# BareBones_Arduino_No_Multiplexer.net
KiCad netlist of a schematic drawn in EAGLE
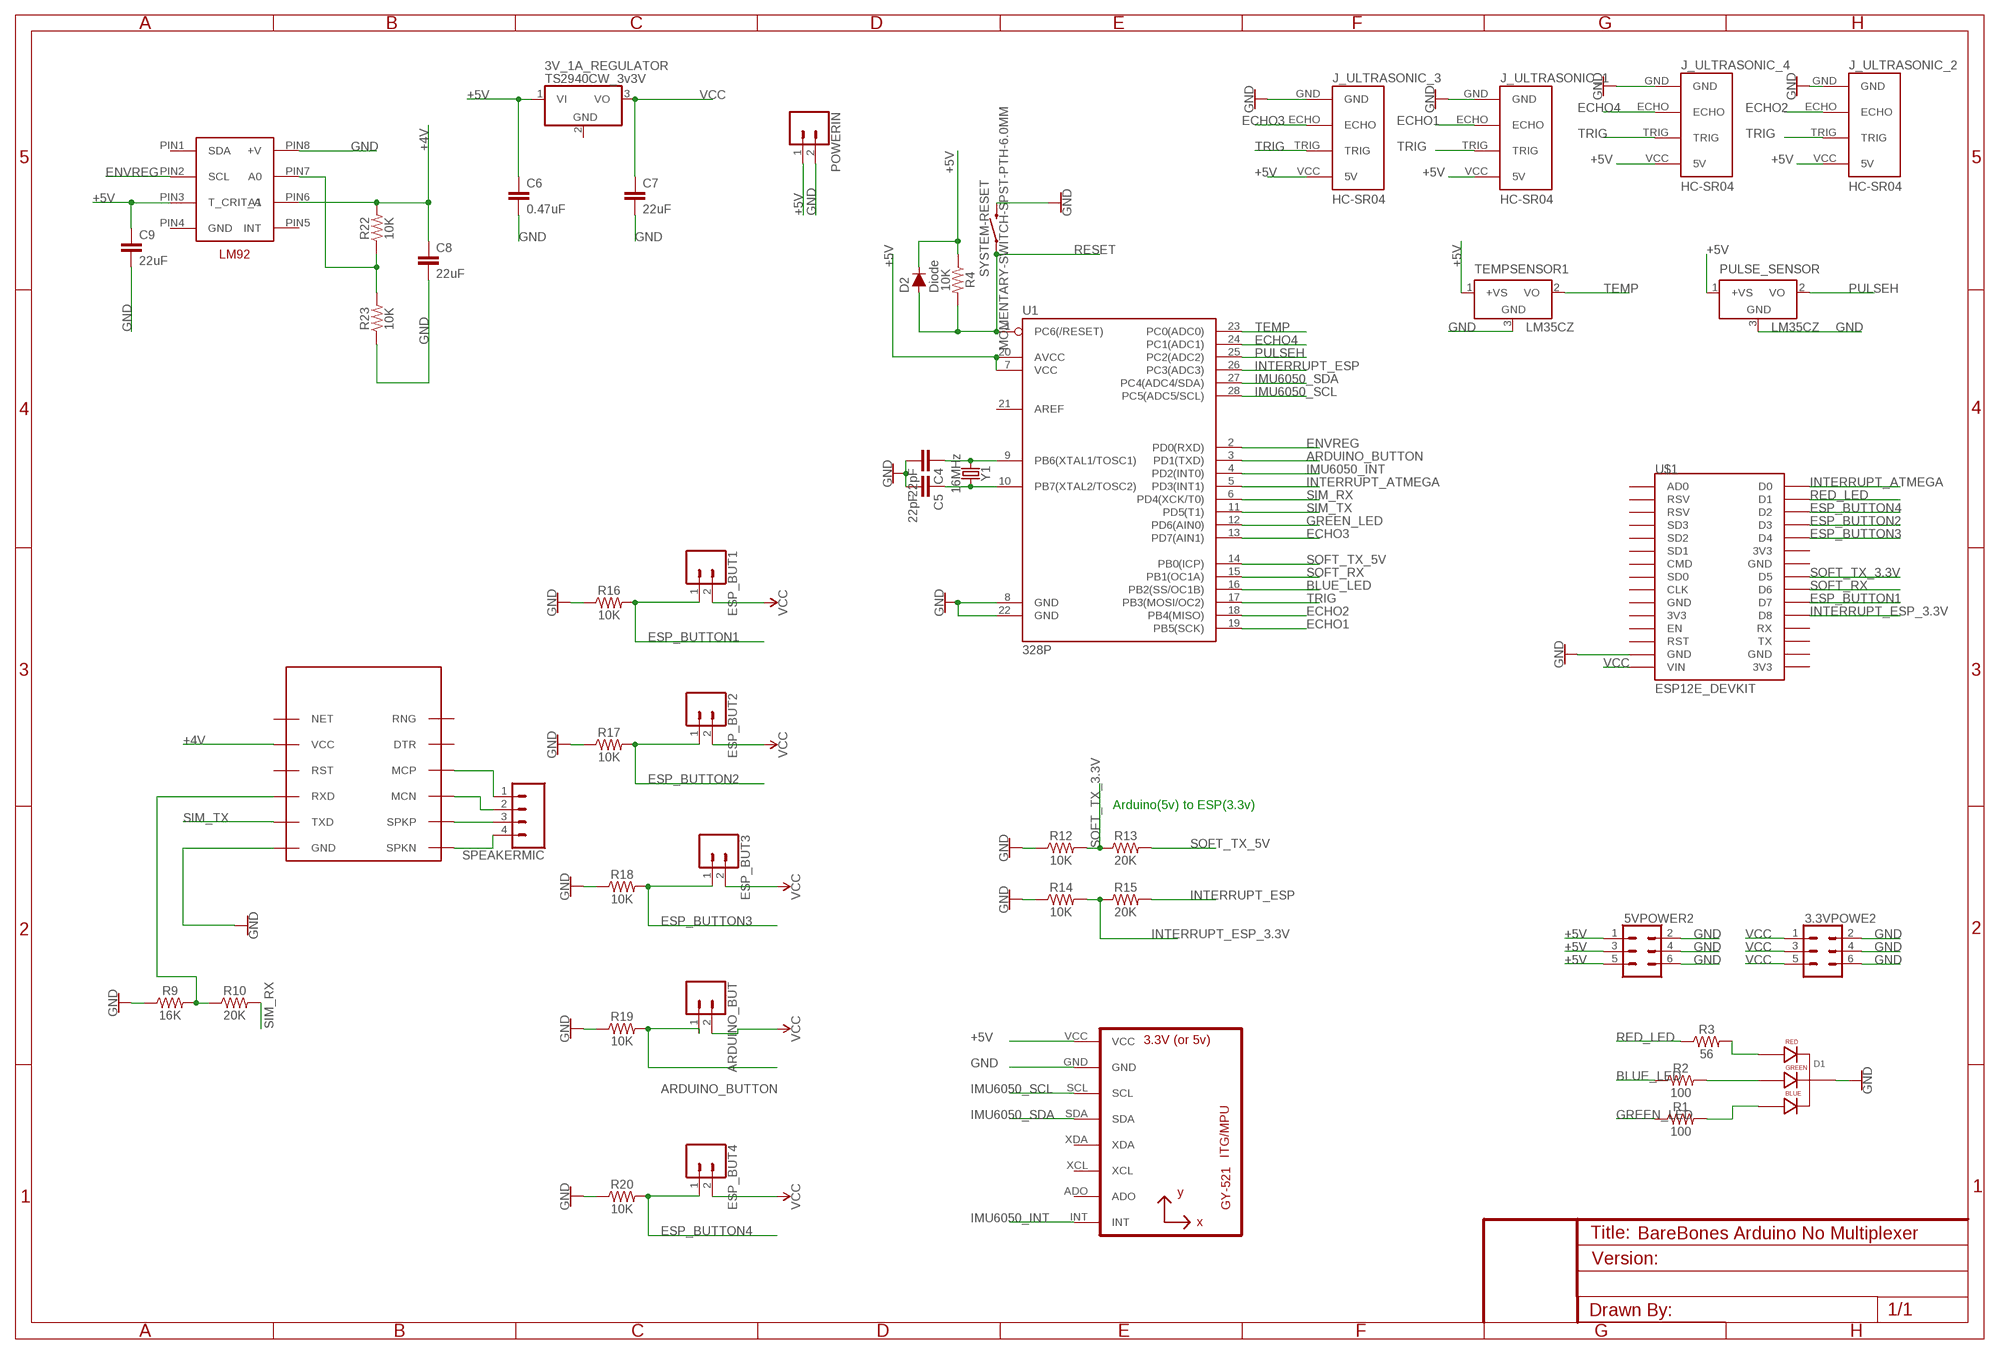
[diagram p0: schematic, sheet 1]

(export (version "E")
  (design (tool "Eeschema 10.0.6"))
  (components
    (comp (ref "3.3VPOWE2")
      (value "CONN_03X2FEMALE")
      (footprint "eagle-import:2X3")
      (libsource (lib "eagle-import") (part "CONN_03X2FEMALE"))
    )
    (comp (ref "3V_1A_REGULATOR")
      (value "TS2940CW_3v3V")
      (footprint "eagle-import:SOT223")
      (libsource (lib "eagle-import") (part "MCP1703DB"))
    )
    (comp (ref "5VPOWER2")
      (value "CONN_03X2FEMALE")
      (footprint "eagle-import:2X3")
      (libsource (lib "eagle-import") (part "CONN_03X2FEMALE"))
    )
    (comp (ref "ARDUINO_BUT")
      (value "CONN_02")
      (footprint "eagle-import:1X02")
      (libsource (lib "eagle-import") (part "CONN_02"))
    )
    (comp (ref "C4")
      (value "22pF")
      (footprint "eagle-import:CAP-PTH-2.54")
      (libsource (lib "eagle-import") (part "22PF-PTH-2.54MM-200V-5%"))
    )
    (comp (ref "C5")
      (value "22pF")
      (footprint "eagle-import:CAP-PTH-2.54")
      (libsource (lib "eagle-import") (part "22PF-PTH-2.54MM-200V-5%"))
    )
    (comp (ref "C6")
      (value "0.47uF")
      (footprint "eagle-import:CAP-PTH-SMALL-KIT")
      (libsource (lib "eagle-import") (part "0.1UF-KIT-EZ-50V-20%"))
    )
    (comp (ref "C7")
      (value "22uF")
      (footprint "eagle-import:CAP-PTH-SMALL-KIT")
      (libsource (lib "eagle-import") (part "0.1UF-KIT-EZ-50V-20%"))
    )
    (comp (ref "C8")
      (value "22uF")
      (footprint "eagle-import:CAP-PTH-SMALL-KIT")
      (libsource (lib "eagle-import") (part "0.1UF-KIT-EZ-50V-20%"))
    )
    (comp (ref "C9")
      (value "22uF")
      (footprint "eagle-import:CAP-PTH-SMALL-KIT")
      (libsource (lib "eagle-import") (part "0.1UF-KIT-EZ-50V-20%"))
    )
    (comp (ref "D1")
      (value "LED-RGB-CC-THRUDIFFUSE")
      (footprint "eagle-import:LED-RGB-THRU")
      (libsource (lib "eagle-import") (part "LED-RGB-CC-THRUDIFFUSE"))
    )
    (comp (ref "D2")
      (value "Diode")
      (footprint "eagle-import:DIODE-1N4148")
      (libsource (lib "eagle-import") (part "DIODE-1N4148"))
    )
    (comp (ref "ESP_BUT1")
      (value "CONN_02")
      (footprint "eagle-import:1X02")
      (libsource (lib "eagle-import") (part "CONN_02"))
    )
    (comp (ref "ESP_BUT2")
      (value "CONN_02")
      (footprint "eagle-import:1X02")
      (libsource (lib "eagle-import") (part "CONN_02"))
    )
    (comp (ref "ESP_BUT3")
      (value "CONN_02")
      (footprint "eagle-import:1X02")
      (libsource (lib "eagle-import") (part "CONN_02"))
    )
    (comp (ref "ESP_BUT4")
      (value "CONN_02")
      (footprint "eagle-import:1X02")
      (libsource (lib "eagle-import") (part "CONN_02"))
    )
    (comp (ref "J_ULTRASONIC_1")
      (value "HC-SR04")
      (footprint "eagle-import:HC-SR04_FOOTPRINT")
      (libsource (lib "eagle-import") (part "HC-SR04"))
    )
    (comp (ref "J_ULTRASONIC_2")
      (value "HC-SR04")
      (footprint "eagle-import:HC-SR04_FOOTPRINT")
      (libsource (lib "eagle-import") (part "HC-SR04"))
    )
    (comp (ref "J_ULTRASONIC_3")
      (value "HC-SR04")
      (footprint "eagle-import:HC-SR04_FOOTPRINT")
      (libsource (lib "eagle-import") (part "HC-SR04"))
    )
    (comp (ref "J_ULTRASONIC_4")
      (value "HC-SR04")
      (footprint "eagle-import:HC-SR04_FOOTPRINT")
      (libsource (lib "eagle-import") (part "HC-SR04"))
    )
    (comp (ref "POWERIN")
      (value "CONN_025MM")
      (footprint "eagle-import:SCREWTERMINAL-5MM-2")
      (libsource (lib "eagle-import") (part "CONN_025MM"))
    )
    (comp (ref "PULSE_SENSOR")
      (value "LM35CZ")
      (footprint "eagle-import:TO92")
      (libsource (lib "eagle-import") (part "LM35CZ"))
    )
    (comp (ref "R1")
      (value "100")
      (footprint "eagle-import:AXIAL-0.3")
      (libsource (lib "eagle-import") (part "100OHM-HORIZ-1/4W-1%"))
    )
    (comp (ref "R2")
      (value "100")
      (footprint "eagle-import:AXIAL-0.3")
      (libsource (lib "eagle-import") (part "100OHM-HORIZ-1/4W-1%"))
    )
    (comp (ref "R3")
      (value "56")
      (footprint "eagle-import:AXIAL-0.3")
      (libsource (lib "eagle-import") (part "RESISTORAXIAL-0.3"))
    )
    (comp (ref "R4")
      (value "10K")
      (footprint "eagle-import:AXIAL-0.3")
      (libsource (lib "eagle-import") (part "100OHM-HORIZ-1/4W-1%"))
    )
    (comp (ref "R9")
      (value "16K")
      (footprint "eagle-import:AXIAL-0.3")
      (libsource (lib "eagle-import") (part "100OHM-HORIZ-1/4W-1%"))
    )
    (comp (ref "R10")
      (value "20K")
      (footprint "eagle-import:AXIAL-0.3")
      (libsource (lib "eagle-import") (part "100OHM-HORIZ-1/4W-1%"))
    )
    (comp (ref "R12")
      (value "10K")
      (footprint "eagle-import:AXIAL-0.3")
      (libsource (lib "eagle-import") (part "100OHM-HORIZ-1/4W-1%"))
    )
    (comp (ref "R13")
      (value "20K")
      (footprint "eagle-import:AXIAL-0.3")
      (libsource (lib "eagle-import") (part "100OHM-HORIZ-1/4W-1%"))
    )
    (comp (ref "R14")
      (value "10K")
      (footprint "eagle-import:AXIAL-0.3")
      (libsource (lib "eagle-import") (part "100OHM-HORIZ-1/4W-1%"))
    )
    (comp (ref "R15")
      (value "20K")
      (footprint "eagle-import:AXIAL-0.3")
      (libsource (lib "eagle-import") (part "100OHM-HORIZ-1/4W-1%"))
    )
    (comp (ref "R16")
      (value "10K")
      (footprint "eagle-import:AXIAL-0.3")
      (libsource (lib "eagle-import") (part "100OHM-HORIZ-1/4W-1%"))
    )
    (comp (ref "R17")
      (value "10K")
      (footprint "eagle-import:AXIAL-0.3")
      (libsource (lib "eagle-import") (part "100OHM-HORIZ-1/4W-1%"))
    )
    (comp (ref "R18")
      (value "10K")
      (footprint "eagle-import:AXIAL-0.3")
      (libsource (lib "eagle-import") (part "100OHM-HORIZ-1/4W-1%"))
    )
    (comp (ref "R19")
      (value "10K")
      (footprint "eagle-import:AXIAL-0.3")
      (libsource (lib "eagle-import") (part "100OHM-HORIZ-1/4W-1%"))
    )
    (comp (ref "R20")
      (value "10K")
      (footprint "eagle-import:AXIAL-0.3")
      (libsource (lib "eagle-import") (part "100OHM-HORIZ-1/4W-1%"))
    )
    (comp (ref "R22")
      (value "10K")
      (footprint "eagle-import:AXIAL-0.3")
      (libsource (lib "eagle-import") (part "100OHM-HORIZ-1/4W-1%"))
    )
    (comp (ref "R23")
      (value "10K")
      (footprint "eagle-import:AXIAL-0.3")
      (libsource (lib "eagle-import") (part "100OHM-HORIZ-1/4W-1%"))
    )
    (comp (ref "SPEAKERMIC")
      (value "CONN_04")
      (footprint "eagle-import:1X04")
      (libsource (lib "eagle-import") (part "CONN_04"))
    )
    (comp (ref "SYSTEM-RESET")
      (value "MOMENTARY-SWITCH-SPST-PTH-6.0MM")
      (footprint "eagle-import:TACTILE_SWITCH_PTH_6.0MM")
      (libsource (lib "eagle-import") (part "MOMENTARY-SWITCH-SPST-PTH-6.0MM"))
    )
    (comp (ref "TEMPSENSOR1")
      (value "LM35CZ")
      (footprint "eagle-import:TO92")
      (libsource (lib "eagle-import") (part "LM35CZ"))
    )
    (comp (ref "U$1")
      (value "ESP12E_DEVKIT")
      (footprint "eagle-import:ESP12E_DEVKIT")
      (libsource (lib "eagle-import") (part "ESP12E_DEVKIT"))
    )
    (comp (ref "U$4")
      (value "SIM800L")
      (footprint "eagle-import:SIM-CORE")
      (libsource (lib "eagle-import") (part "SIM800L"))
    )
    (comp (ref "U1")
      (value "328P")
      (footprint "eagle-import:DIP28")
      (libsource (lib "eagle-import") (part "ATMEGA328P_PDIP"))
    )
    (comp (ref "U2")
      (value "GY-521MPU6050")
      (footprint "eagle-import:GY-521")
      (libsource (lib "eagle-import") (part "GY-521MPU6050"))
    )
    (comp (ref "VREG")
      (value "LM92")
      (footprint "eagle-import:SOP-8")
      (fields (field (name "SPICEPREFIX") "X"))
      (libsource (lib "eagle-import") (part "LM92"))
    )
    (comp (ref "Y1")
      (value "16MHz")
      (footprint "eagle-import:HC49US")
      (libsource (lib "eagle-import") (part "CRYSTAL-16MHZPTH-HC49US"))
    )
  )
  (nets
    (net (code "1") (name "/+4V") (class "Default")
      (node (ref "C8") (pin "1") (pinfunction "1_1") (pintype "passive"))
      (node (ref "R22") (pin "P$2") (pinfunction "2_P$2") (pintype "passive"))
      (node (ref "U$4") (pin "VCC") (pinfunction "VCC_VCC") (pintype "bidirectional"))
      (node (ref "VREG") (pin "PIN6") (pinfunction "A1_PIN6") (pintype "bidirectional"))
    )
    (net (code "2") (name "/+5V") (class "Default")
      (node (ref "3V_1A_REGULATOR") (pin "1") (pinfunction "VI_1") (pintype "input"))
      (node (ref "5VPOWER2") (pin "1") (pinfunction "1_1") (pintype "bidirectional"))
      (node (ref "5VPOWER2") (pin "3") (pinfunction "3_3") (pintype "bidirectional"))
      (node (ref "5VPOWER2") (pin "5") (pinfunction "5_5") (pintype "bidirectional"))
      (node (ref "C6") (pin "1") (pinfunction "1_1") (pintype "passive"))
      (node (ref "C9") (pin "1") (pinfunction "1_1") (pintype "passive"))
      (node (ref "D2") (pin "C") (pinfunction "C_C") (pintype "passive"))
      (node (ref "J_ULTRASONIC_1") (pin "VCC") (pinfunction "5V_VCC") (pintype "bidirectional"))
      (node (ref "J_ULTRASONIC_2") (pin "VCC") (pinfunction "5V_VCC") (pintype "bidirectional"))
      (node (ref "J_ULTRASONIC_3") (pin "VCC") (pinfunction "5V_VCC") (pintype "bidirectional"))
      (node (ref "J_ULTRASONIC_4") (pin "VCC") (pinfunction "5V_VCC") (pintype "bidirectional"))
      (node (ref "POWERIN") (pin "1") (pinfunction "1_1") (pintype "passive"))
      (node (ref "PULSE_SENSOR") (pin "1") (pinfunction "+VS_1") (pintype "input"))
      (node (ref "R4") (pin "P$1") (pinfunction "1_P$1") (pintype "passive"))
      (node (ref "TEMPSENSOR1") (pin "1") (pinfunction "+VS_1") (pintype "input"))
      (node (ref "U1") (pin "20") (pinfunction "AVCC_20") (pintype "bidirectional"))
      (node (ref "U1") (pin "7") (pinfunction "VCC_7") (pintype "bidirectional"))
      (node (ref "U2") (pin "VCC") (pinfunction "VCC_VCC") (pintype "bidirectional"))
      (node (ref "VREG") (pin "PIN3") (pinfunction "T_CRIT_A_PIN3") (pintype "bidirectional"))
    )
    (net (code "3") (name "/ARDUINO_BUTTON") (class "Default")
      (node (ref "ARDUINO_BUT") (pin "1") (pinfunction "1_1") (pintype "passive"))
      (node (ref "R19") (pin "P$2") (pinfunction "2_P$2") (pintype "passive"))
      (node (ref "U1") (pin "3") (pinfunction "PD1(TXD)_3") (pintype "bidirectional"))
    )
    (net (code "4") (name "/BLUE_LED") (class "Default")
      (node (ref "R2") (pin "P$1") (pinfunction "1_P$1") (pintype "passive"))
      (node (ref "U1") (pin "16") (pinfunction "PB2(SS/OC1B)_16") (pintype "bidirectional"))
    )
    (net (code "5") (name "/ECHO1") (class "Default")
      (node (ref "J_ULTRASONIC_1") (pin "ECHO") (pinfunction "ECHO_ECHO") (pintype "bidirectional"))
      (node (ref "U1") (pin "19") (pinfunction "PB5(SCK)_19") (pintype "bidirectional"))
    )
    (net (code "6") (name "/ECHO2") (class "Default")
      (node (ref "J_ULTRASONIC_2") (pin "ECHO") (pinfunction "ECHO_ECHO") (pintype "bidirectional"))
      (node (ref "U1") (pin "18") (pinfunction "PB4(MISO)_18") (pintype "bidirectional"))
    )
    (net (code "7") (name "/ECHO3") (class "Default")
      (node (ref "J_ULTRASONIC_3") (pin "ECHO") (pinfunction "ECHO_ECHO") (pintype "bidirectional"))
      (node (ref "U1") (pin "13") (pinfunction "PD7(AIN1)_13") (pintype "bidirectional"))
    )
    (net (code "8") (name "/ECHO4") (class "Default")
      (node (ref "J_ULTRASONIC_4") (pin "ECHO") (pinfunction "ECHO_ECHO") (pintype "bidirectional"))
      (node (ref "U1") (pin "24") (pinfunction "PC1(ADC1)_24") (pintype "bidirectional"))
    )
    (net (code "9") (name "/ENVREG") (class "Default")
      (node (ref "U1") (pin "2") (pinfunction "PD0(RXD)_2") (pintype "bidirectional"))
      (node (ref "VREG") (pin "PIN2") (pinfunction "SCL_PIN2") (pintype "bidirectional"))
    )
    (net (code "10") (name "/ESP_BUTTON1") (class "Default")
      (node (ref "ESP_BUT1") (pin "1") (pinfunction "1_1") (pintype "passive"))
      (node (ref "R16") (pin "P$2") (pinfunction "2_P$2") (pintype "passive"))
      (node (ref "U$1") (pin "D7") (pinfunction "D7_D7") (pintype "bidirectional"))
    )
    (net (code "11") (name "/ESP_BUTTON2") (class "Default")
      (node (ref "ESP_BUT2") (pin "1") (pinfunction "1_1") (pintype "passive"))
      (node (ref "R17") (pin "P$2") (pinfunction "2_P$2") (pintype "passive"))
      (node (ref "U$1") (pin "D3") (pinfunction "D3_D3") (pintype "bidirectional"))
    )
    (net (code "12") (name "/ESP_BUTTON3") (class "Default")
      (node (ref "ESP_BUT3") (pin "1") (pinfunction "1_1") (pintype "passive"))
      (node (ref "R18") (pin "P$2") (pinfunction "2_P$2") (pintype "passive"))
      (node (ref "U$1") (pin "D4") (pinfunction "D4_D4") (pintype "bidirectional"))
    )
    (net (code "13") (name "/ESP_BUTTON4") (class "Default")
      (node (ref "ESP_BUT4") (pin "1") (pinfunction "1_1") (pintype "passive"))
      (node (ref "R20") (pin "P$2") (pinfunction "2_P$2") (pintype "passive"))
      (node (ref "U$1") (pin "D2") (pinfunction "D2_D2") (pintype "bidirectional"))
    )
    (net (code "14") (name "/GREEN_LED") (class "Default")
      (node (ref "R1") (pin "P$1") (pinfunction "1_P$1") (pintype "passive"))
      (node (ref "U1") (pin "12") (pinfunction "PD6(AIN0)_12") (pintype "bidirectional"))
    )
    (net (code "15") (name "/IMU6050_INT") (class "Default")
      (node (ref "U1") (pin "4") (pinfunction "PD2(INT0)_4") (pintype "bidirectional"))
      (node (ref "U2") (pin "INT") (pinfunction "INT_INT") (pintype "bidirectional"))
    )
    (net (code "16") (name "/IMU6050_SCL") (class "Default")
      (node (ref "U1") (pin "28") (pinfunction "PC5(ADC5/SCL)_28") (pintype "bidirectional"))
      (node (ref "U2") (pin "SCL") (pinfunction "SCL_SCL") (pintype "bidirectional"))
    )
    (net (code "17") (name "/IMU6050_SDA") (class "Default")
      (node (ref "U1") (pin "27") (pinfunction "PC4(ADC4/SDA)_27") (pintype "bidirectional"))
      (node (ref "U2") (pin "SDA") (pinfunction "SDA_SDA") (pintype "bidirectional"))
    )
    (net (code "18") (name "/INTERRUPT_ATMEGA") (class "Default")
      (node (ref "U$1") (pin "D0") (pinfunction "D0_D0") (pintype "bidirectional"))
      (node (ref "U1") (pin "5") (pinfunction "PD3(INT1)_5") (pintype "bidirectional"))
    )
    (net (code "19") (name "/INTERRUPT_ESP") (class "Default")
      (node (ref "R15") (pin "P$2") (pinfunction "2_P$2") (pintype "passive"))
      (node (ref "U1") (pin "26") (pinfunction "PC3(ADC3)_26") (pintype "bidirectional"))
    )
    (net (code "20") (name "/INTERRUPT_ESP_3.3V") (class "Default")
      (node (ref "R14") (pin "P$2") (pinfunction "2_P$2") (pintype "passive"))
      (node (ref "R15") (pin "P$1") (pinfunction "1_P$1") (pintype "passive"))
      (node (ref "U$1") (pin "D8") (pinfunction "D8_D8") (pintype "bidirectional"))
    )
    (net (code "21") (name "/PULSEH") (class "Default")
      (node (ref "PULSE_SENSOR") (pin "2") (pinfunction "VO_2") (pintype "input"))
      (node (ref "U1") (pin "25") (pinfunction "PC2(ADC2)_25") (pintype "bidirectional"))
    )
    (net (code "22") (name "/RED_LED") (class "Default")
      (node (ref "R3") (pin "P$1") (pinfunction "1_P$1") (pintype "passive"))
      (node (ref "U$1") (pin "D1") (pinfunction "D1_D1") (pintype "bidirectional"))
    )
    (net (code "23") (name "/RESET") (class "Default")
      (node (ref "D2") (pin "A") (pinfunction "A_A") (pintype "passive"))
      (node (ref "R4") (pin "P$2") (pinfunction "2_P$2") (pintype "passive"))
      (node (ref "SYSTEM-RESET") (pin "1") (pinfunction "1_1") (pintype "passive"))
      (node (ref "U1") (pin "1") (pinfunction "PC6(/RESET)_1") (pintype "bidirectional"))
    )
    (net (code "24") (name "/SIM_RX") (class "Default")
      (node (ref "R10") (pin "P$2") (pinfunction "2_P$2") (pintype "passive"))
      (node (ref "U1") (pin "6") (pinfunction "PD4(XCK/T0)_6") (pintype "bidirectional"))
    )
    (net (code "25") (name "/SIM_TX") (class "Default")
      (node (ref "U$4") (pin "TXD") (pinfunction "TXD_TXD") (pintype "bidirectional"))
      (node (ref "U1") (pin "11") (pinfunction "PD5(T1)_11") (pintype "bidirectional"))
    )
    (net (code "26") (name "/SOFT_RX") (class "Default")
      (node (ref "U$1") (pin "D6") (pinfunction "D6_D6") (pintype "bidirectional"))
      (node (ref "U1") (pin "15") (pinfunction "PB1(OC1A)_15") (pintype "bidirectional"))
    )
    (net (code "27") (name "/SOFT_TX_3.3V") (class "Default")
      (node (ref "R12") (pin "P$2") (pinfunction "2_P$2") (pintype "passive"))
      (node (ref "R13") (pin "P$1") (pinfunction "1_P$1") (pintype "passive"))
      (node (ref "U$1") (pin "D5") (pinfunction "D5_D5") (pintype "bidirectional"))
    )
    (net (code "28") (name "/SOFT_TX_5V") (class "Default")
      (node (ref "R13") (pin "P$2") (pinfunction "2_P$2") (pintype "passive"))
      (node (ref "U1") (pin "14") (pinfunction "PB0(ICP)_14") (pintype "bidirectional"))
    )
    (net (code "29") (name "/TEMP") (class "Default")
      (node (ref "TEMPSENSOR1") (pin "2") (pinfunction "VO_2") (pintype "input"))
      (node (ref "U1") (pin "23") (pinfunction "PC0(ADC0)_23") (pintype "bidirectional"))
    )
    (net (code "30") (name "/TRIG") (class "Default")
      (node (ref "J_ULTRASONIC_1") (pin "TRIG") (pinfunction "TRIG_TRIG") (pintype "bidirectional"))
      (node (ref "J_ULTRASONIC_2") (pin "TRIG") (pinfunction "TRIG_TRIG") (pintype "bidirectional"))
      (node (ref "J_ULTRASONIC_3") (pin "TRIG") (pinfunction "TRIG_TRIG") (pintype "bidirectional"))
      (node (ref "J_ULTRASONIC_4") (pin "TRIG") (pinfunction "TRIG_TRIG") (pintype "bidirectional"))
      (node (ref "U1") (pin "17") (pinfunction "PB3(MOSI/OC2)_17") (pintype "bidirectional"))
    )
    (net (code "31") (name "GND") (class "Default")
      (node (ref "3.3VPOWE2") (pin "2") (pinfunction "2_2") (pintype "bidirectional"))
      (node (ref "3.3VPOWE2") (pin "4") (pinfunction "4_4") (pintype "bidirectional"))
      (node (ref "3.3VPOWE2") (pin "6") (pinfunction "6_6") (pintype "bidirectional"))
      (node (ref "5VPOWER2") (pin "2") (pinfunction "2_2") (pintype "bidirectional"))
      (node (ref "5VPOWER2") (pin "4") (pinfunction "4_4") (pintype "bidirectional"))
      (node (ref "5VPOWER2") (pin "6") (pinfunction "6_6") (pintype "bidirectional"))
      (node (ref "C4") (pin "2") (pinfunction "2_2") (pintype "passive"))
      (node (ref "C5") (pin "2") (pinfunction "2_2") (pintype "passive"))
      (node (ref "C6") (pin "2") (pinfunction "2_2") (pintype "passive"))
      (node (ref "C7") (pin "2") (pinfunction "2_2") (pintype "passive"))
      (node (ref "C8") (pin "2") (pinfunction "2_2") (pintype "passive"))
      (node (ref "C9") (pin "2") (pinfunction "2_2") (pintype "passive"))
      (node (ref "D1") (pin "2") (pinfunction "CATHODE_2") (pintype "bidirectional"))
      (node (ref "J_ULTRASONIC_1") (pin "GND") (pinfunction "GND_GND") (pintype "bidirectional"))
      (node (ref "J_ULTRASONIC_2") (pin "GND") (pinfunction "GND_GND") (pintype "bidirectional"))
      (node (ref "J_ULTRASONIC_3") (pin "GND") (pinfunction "GND_GND") (pintype "bidirectional"))
      (node (ref "J_ULTRASONIC_4") (pin "GND") (pinfunction "GND_GND") (pintype "bidirectional"))
      (node (ref "POWERIN") (pin "2") (pinfunction "2_2") (pintype "passive"))
      (node (ref "PULSE_SENSOR") (pin "3") (pinfunction "GND_3") (pintype "power_in"))
      (node (ref "R12") (pin "P$1") (pinfunction "1_P$1") (pintype "passive"))
      (node (ref "R14") (pin "P$1") (pinfunction "1_P$1") (pintype "passive"))
      (node (ref "R16") (pin "P$1") (pinfunction "1_P$1") (pintype "passive"))
      (node (ref "R17") (pin "P$1") (pinfunction "1_P$1") (pintype "passive"))
      (node (ref "R18") (pin "P$1") (pinfunction "1_P$1") (pintype "passive"))
      (node (ref "R19") (pin "P$1") (pinfunction "1_P$1") (pintype "passive"))
      (node (ref "R20") (pin "P$1") (pinfunction "1_P$1") (pintype "passive"))
      (node (ref "R23") (pin "P$1") (pinfunction "1_P$1") (pintype "passive"))
      (node (ref "R9") (pin "P$1") (pinfunction "1_P$1") (pintype "passive"))
      (node (ref "SYSTEM-RESET") (pin "3") (pinfunction "2_3") (pintype "passive"))
      (node (ref "TEMPSENSOR1") (pin "3") (pinfunction "GND_3") (pintype "power_in"))
      (node (ref "U$1") (pin "GND@1") (pinfunction "GND_GND@1") (pintype "bidirectional"))
      (node (ref "U$4") (pin "GND") (pinfunction "GND_GND") (pintype "bidirectional"))
      (node (ref "U1") (pin "22") (pinfunction "GND_22") (pintype "bidirectional"))
      (node (ref "U1") (pin "8") (pinfunction "GND_8") (pintype "bidirectional"))
      (node (ref "U2") (pin "GND") (pinfunction "GND_GND") (pintype "bidirectional"))
      (node (ref "VREG") (pin "PIN8") (pinfunction "+V_PIN8") (pintype "bidirectional"))
    )
    (net (code "32") (name "Net-(D1-BLUE_CATHODE)") (class "Default")
      (node (ref "D1") (pin "4") (pinfunction "BLUE_CATHODE_4") (pintype "bidirectional"))
      (node (ref "R1") (pin "P$2") (pinfunction "2_P$2") (pintype "passive"))
    )
    (net (code "33") (name "Net-(D1-GREEN_CATHODE)") (class "Default")
      (node (ref "D1") (pin "3") (pinfunction "GREEN_CATHODE_3") (pintype "bidirectional"))
      (node (ref "R2") (pin "P$2") (pinfunction "2_P$2") (pintype "passive"))
    )
    (net (code "34") (name "Net-(D1-RED_CATHODE)") (class "Default")
      (node (ref "D1") (pin "1") (pinfunction "RED_CATHODE_1") (pintype "bidirectional"))
      (node (ref "R3") (pin "P$2") (pinfunction "2_P$2") (pintype "passive"))
    )
    (net (code "35") (name "Net-(R10-1)") (class "Default")
      (node (ref "R10") (pin "P$1") (pinfunction "1_P$1") (pintype "passive"))
      (node (ref "R9") (pin "P$2") (pinfunction "2_P$2") (pintype "passive"))
      (node (ref "U$4") (pin "RXD") (pinfunction "RXD_RXD") (pintype "bidirectional"))
    )
    (net (code "36") (name "Net-(R22-1)") (class "Default")
      (node (ref "R22") (pin "P$1") (pinfunction "1_P$1") (pintype "passive"))
      (node (ref "R23") (pin "P$2") (pinfunction "2_P$2") (pintype "passive"))
      (node (ref "VREG") (pin "PIN7") (pinfunction "A0_PIN7") (pintype "bidirectional"))
    )
    (net (code "37") (name "Net-(SPEAKERMIC-Pad1)") (class "Default")
      (node (ref "SPEAKERMIC") (pin "1") (pinfunction "1_1") (pintype "passive"))
      (node (ref "U$4") (pin "MCP") (pinfunction "MCP_MCP") (pintype "bidirectional"))
    )
    (net (code "38") (name "Net-(SPEAKERMIC-Pad2)") (class "Default")
      (node (ref "SPEAKERMIC") (pin "2") (pinfunction "2_2") (pintype "passive"))
      (node (ref "U$4") (pin "MCN") (pinfunction "MCN_MCN") (pintype "bidirectional"))
    )
    (net (code "39") (name "Net-(SPEAKERMIC-Pad3)") (class "Default")
      (node (ref "SPEAKERMIC") (pin "3") (pinfunction "3_3") (pintype "passive"))
      (node (ref "U$4") (pin "SPKP") (pinfunction "SPKP_SPKP") (pintype "bidirectional"))
    )
    (net (code "40") (name "Net-(SPEAKERMIC-Pad4)") (class "Default")
      (node (ref "SPEAKERMIC") (pin "4") (pinfunction "4_4") (pintype "passive"))
      (node (ref "U$4") (pin "SPKN") (pinfunction "SPKN_SPKN") (pintype "bidirectional"))
    )
    (net (code "41") (name "Net-(U1-PB6(XTAL1{slash}TOSC1))") (class "Default")
      (node (ref "C4") (pin "1") (pinfunction "1_1") (pintype "passive"))
      (node (ref "U1") (pin "9") (pinfunction "PB6(XTAL1/TOSC1)_9") (pintype "bidirectional"))
      (node (ref "Y1") (pin "1") (pinfunction "1_1") (pintype "passive"))
    )
    (net (code "42") (name "Net-(U1-PB7(XTAL2{slash}TOSC2))") (class "Default")
      (node (ref "C5") (pin "1") (pinfunction "1_1") (pintype "passive"))
      (node (ref "U1") (pin "10") (pinfunction "PB7(XTAL2/TOSC2)_10") (pintype "bidirectional"))
      (node (ref "Y1") (pin "2") (pinfunction "2_2") (pintype "passive"))
    )
    (net (code "43") (name "VCC") (class "Default")
      (node (ref "3.3VPOWE2") (pin "1") (pinfunction "1_1") (pintype "bidirectional"))
      (node (ref "3.3VPOWE2") (pin "3") (pinfunction "3_3") (pintype "bidirectional"))
      (node (ref "3.3VPOWE2") (pin "5") (pinfunction "5_5") (pintype "bidirectional"))
      (node (ref "3V_1A_REGULATOR") (pin "3") (pinfunction "VO_3") (pintype "passive"))
      (node (ref "ARDUINO_BUT") (pin "2") (pinfunction "2_2") (pintype "passive"))
      (node (ref "C7") (pin "1") (pinfunction "1_1") (pintype "passive"))
      (node (ref "ESP_BUT1") (pin "2") (pinfunction "2_2") (pintype "passive"))
      (node (ref "ESP_BUT2") (pin "2") (pinfunction "2_2") (pintype "passive"))
      (node (ref "ESP_BUT3") (pin "2") (pinfunction "2_2") (pintype "passive"))
      (node (ref "ESP_BUT4") (pin "2") (pinfunction "2_2") (pintype "passive"))
      (node (ref "U$1") (pin "VIN") (pinfunction "VIN_VIN") (pintype "bidirectional"))
    )
    (net (code "44") (name "unconnected-(3V_1A_REGULATOR-GND-Pad2)") (class "Default")
      (node (ref "3V_1A_REGULATOR") (pin "2") (pinfunction "GND_2") (pintype "passive"))
    )
    (net (code "45") (name "unconnected-(U$1-3V3-Pad3V3@0)") (class "Default")
      (node (ref "U$1") (pin "3V3@0") (pinfunction "3V3_3V3@0") (pintype "bidirectional"))
    )
    (net (code "46") (name "unconnected-(U$1-3V3-Pad3V3@1)") (class "Default")
      (node (ref "U$1") (pin "3V3@1") (pinfunction "3V3_3V3@1") (pintype "bidirectional"))
    )
    (net (code "47") (name "unconnected-(U$1-3V3-Pad3V3@2)") (class "Default")
      (node (ref "U$1") (pin "3V3@2") (pinfunction "3V3_3V3@2") (pintype "bidirectional"))
    )
    (net (code "48") (name "unconnected-(U$1-GND-PadGND@0)") (class "Default")
      (node (ref "U$1") (pin "GND@0") (pinfunction "GND_GND@0") (pintype "bidirectional"))
    )
    (net (code "49") (name "unconnected-(U$1-GND-PadGND@2)") (class "Default")
      (node (ref "U$1") (pin "GND@2") (pinfunction "GND_GND@2") (pintype "bidirectional"))
    )
    (net (code "50") (name "unconnected-(U$1-GND-PadGND@3)") (class "Default")
      (node (ref "U$1") (pin "GND@3") (pinfunction "GND_GND@3") (pintype "bidirectional"))
    )
    (net (code "51") (name "unconnected-(U$1-PadAD0)") (class "Default")
      (node (ref "U$1") (pin "AD0") (pinfunction "AD0_AD0") (pintype "bidirectional"))
    )
    (net (code "52") (name "unconnected-(U$1-PadCLK)") (class "Default")
      (node (ref "U$1") (pin "CLK") (pinfunction "CLK_CLK") (pintype "bidirectional"))
    )
    (net (code "53") (name "unconnected-(U$1-PadCMD)") (class "Default")
      (node (ref "U$1") (pin "CMD") (pinfunction "CMD_CMD") (pintype "bidirectional"))
    )
    (net (code "54") (name "unconnected-(U$1-PadEN)") (class "Default")
      (node (ref "U$1") (pin "EN") (pinfunction "EN_EN") (pintype "bidirectional"))
    )
    (net (code "55") (name "unconnected-(U$1-PadRST)") (class "Default")
      (node (ref "U$1") (pin "RST") (pinfunction "RST_RST") (pintype "bidirectional"))
    )
    (net (code "56") (name "unconnected-(U$1-PadRX)") (class "Default")
      (node (ref "U$1") (pin "RX") (pinfunction "RX_RX") (pintype "bidirectional"))
    )
    (net (code "57") (name "unconnected-(U$1-PadSD0)") (class "Default")
      (node (ref "U$1") (pin "SD0") (pinfunction "SD0_SD0") (pintype "bidirectional"))
    )
    (net (code "58") (name "unconnected-(U$1-PadSD1)") (class "Default")
      (node (ref "U$1") (pin "SD1") (pinfunction "SD1_SD1") (pintype "bidirectional"))
    )
    (net (code "59") (name "unconnected-(U$1-PadSD2)") (class "Default")
      (node (ref "U$1") (pin "SD2") (pinfunction "SD2_SD2") (pintype "bidirectional"))
    )
    (net (code "60") (name "unconnected-(U$1-PadSD3)") (class "Default")
      (node (ref "U$1") (pin "SD3") (pinfunction "SD3_SD3") (pintype "bidirectional"))
    )
    (net (code "61") (name "unconnected-(U$1-PadTX)") (class "Default")
      (node (ref "U$1") (pin "TX") (pinfunction "TX_TX") (pintype "bidirectional"))
    )
    (net (code "62") (name "unconnected-(U$1-RSV-PadRSV@0)") (class "Default")
      (node (ref "U$1") (pin "RSV@0") (pinfunction "RSV_RSV@0") (pintype "bidirectional"))
    )
    (net (code "63") (name "unconnected-(U$1-RSV-PadRSV@1)") (class "Default")
      (node (ref "U$1") (pin "RSV@1") (pinfunction "RSV_RSV@1") (pintype "bidirectional"))
    )
    (net (code "64") (name "unconnected-(U$4-PadDTR)") (class "Default")
      (node (ref "U$4") (pin "DTR") (pinfunction "DTR_DTR") (pintype "bidirectional"))
    )
    (net (code "65") (name "unconnected-(U$4-PadNET)") (class "Default")
      (node (ref "U$4") (pin "NET") (pinfunction "NET_NET") (pintype "bidirectional"))
    )
    (net (code "66") (name "unconnected-(U$4-PadRNG)") (class "Default")
      (node (ref "U$4") (pin "RNG") (pinfunction "RNG_RNG") (pintype "bidirectional"))
    )
    (net (code "67") (name "unconnected-(U$4-PadRST)") (class "Default")
      (node (ref "U$4") (pin "RST") (pinfunction "RST_RST") (pintype "bidirectional"))
    )
    (net (code "68") (name "unconnected-(U1-AREF-Pad21)") (class "Default")
      (node (ref "U1") (pin "21") (pinfunction "AREF_21") (pintype "bidirectional"))
    )
    (net (code "69") (name "unconnected-(U2-PadADO)") (class "Default")
      (node (ref "U2") (pin "ADO") (pinfunction "ADO_ADO") (pintype "bidirectional"))
    )
    (net (code "70") (name "unconnected-(U2-PadXCL)") (class "Default")
      (node (ref "U2") (pin "XCL") (pinfunction "XCL_XCL") (pintype "bidirectional"))
    )
    (net (code "71") (name "unconnected-(U2-PadXDA)") (class "Default")
      (node (ref "U2") (pin "XDA") (pinfunction "XDA_XDA") (pintype "bidirectional"))
    )
    (net (code "72") (name "unconnected-(VREG-GND-PadPIN4)") (class "Default")
      (node (ref "VREG") (pin "PIN4") (pinfunction "GND_PIN4") (pintype "bidirectional"))
    )
    (net (code "73") (name "unconnected-(VREG-INT-PadPIN5)") (class "Default")
      (node (ref "VREG") (pin "PIN5") (pinfunction "INT_PIN5") (pintype "bidirectional"))
    )
    (net (code "74") (name "unconnected-(VREG-SDA-PadPIN1)") (class "Default")
      (node (ref "VREG") (pin "PIN1") (pinfunction "SDA_PIN1") (pintype "bidirectional"))
    )
  )
)
